# H26R00.net
KiCad netlist of a schematic drawn in EAGLE
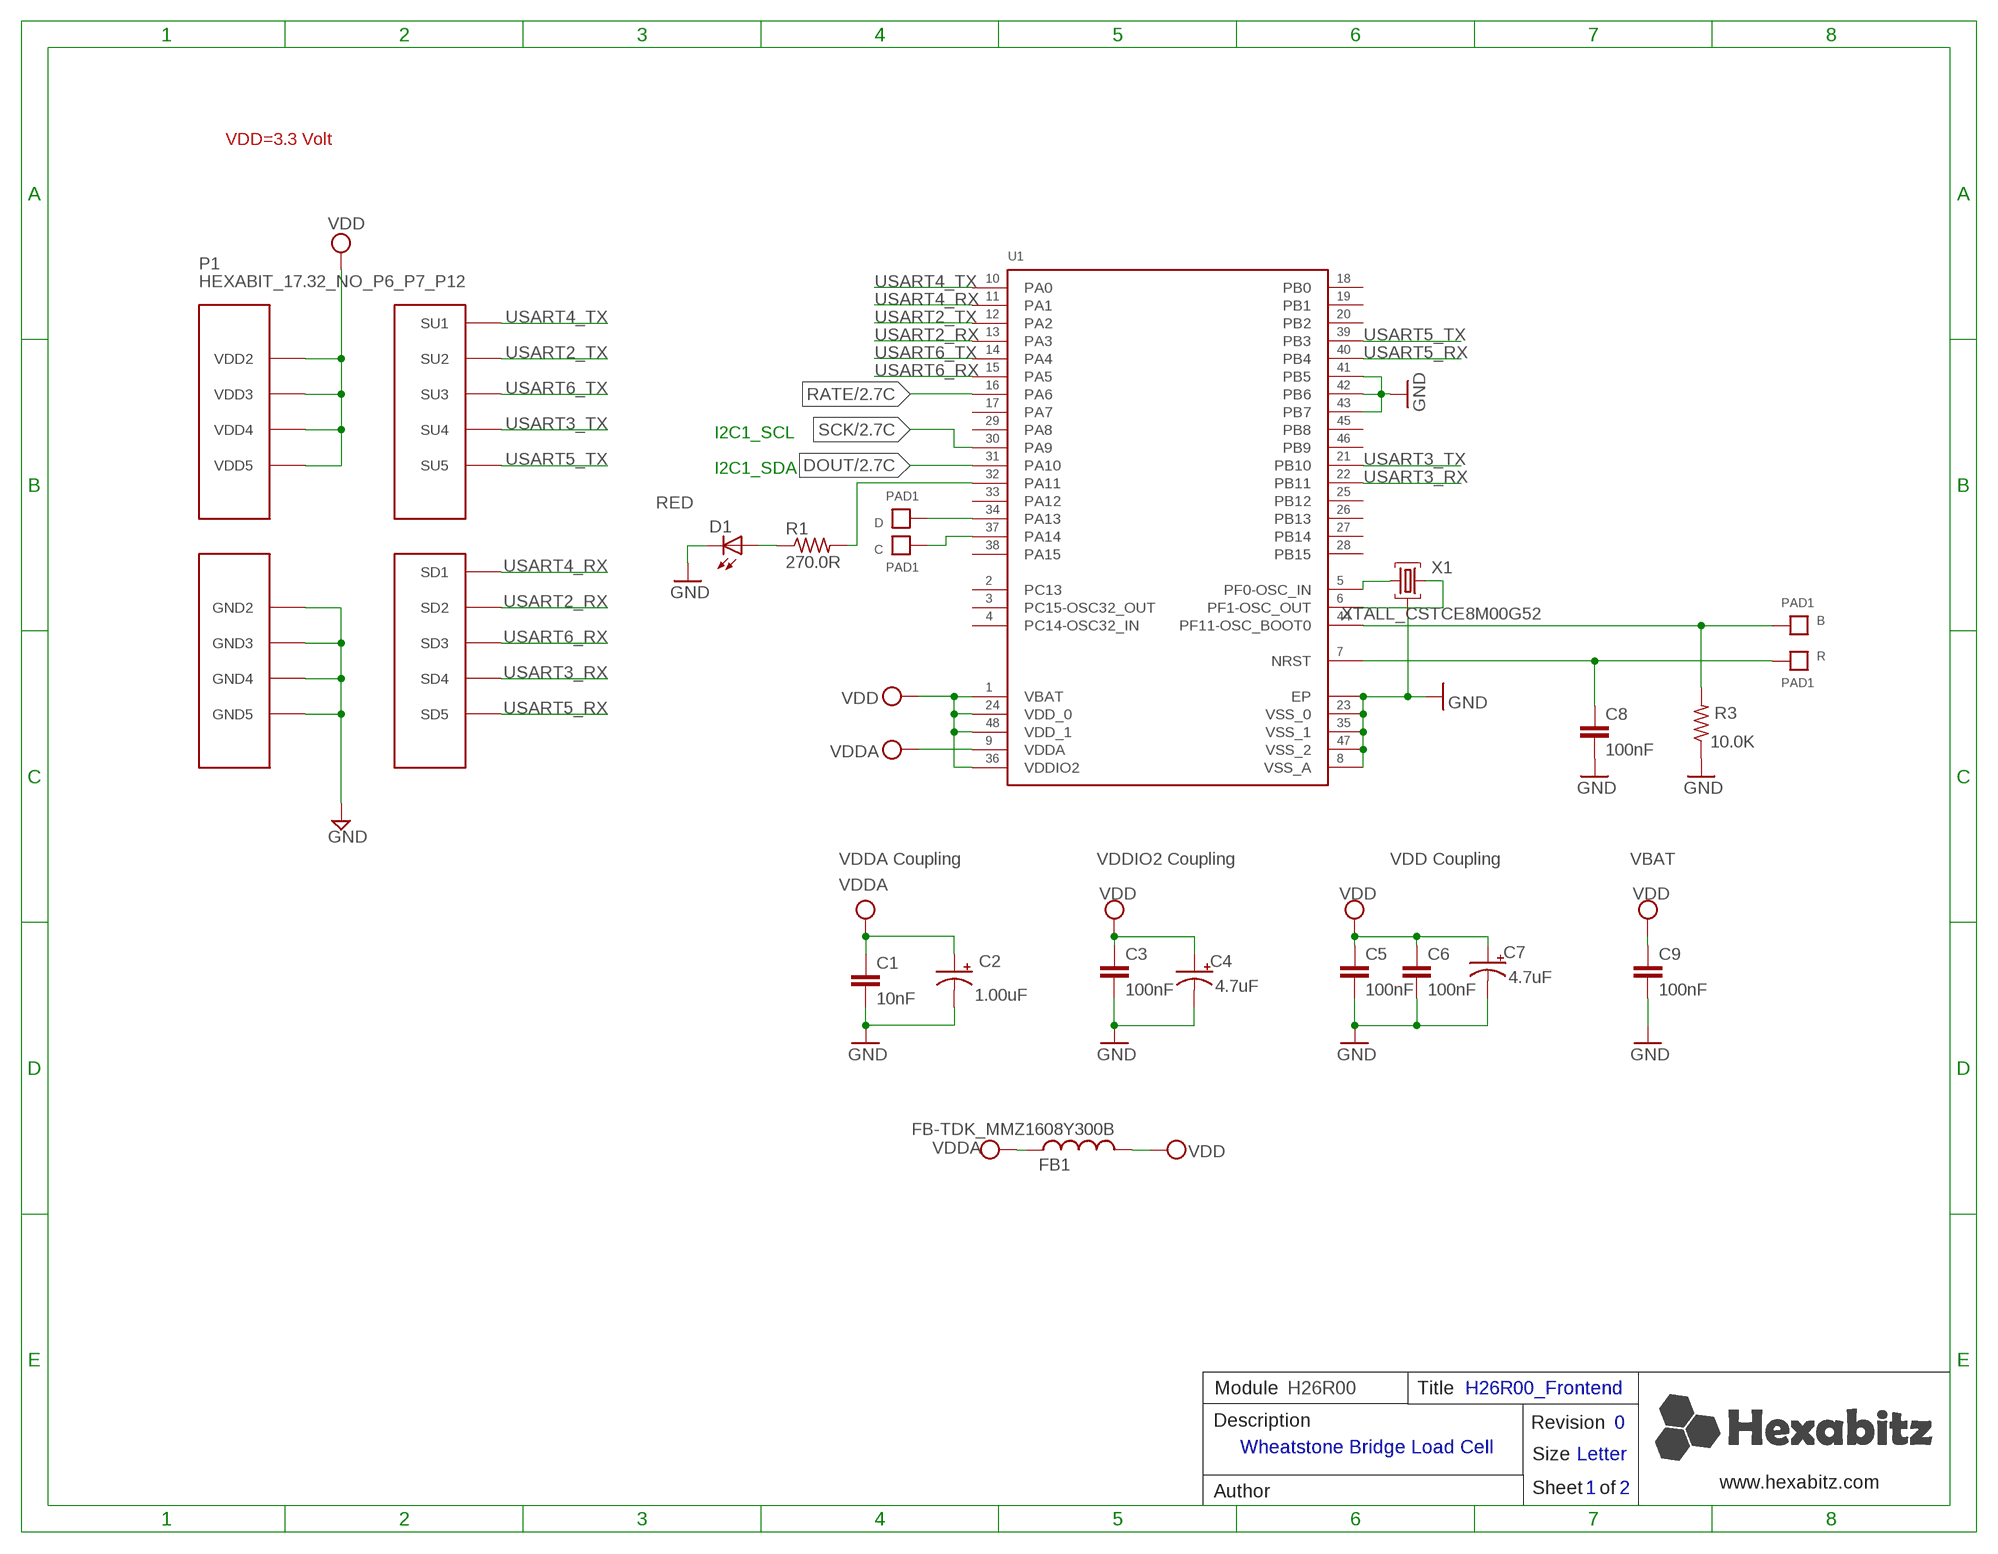
[diagram p0: schematic, sheet 1]
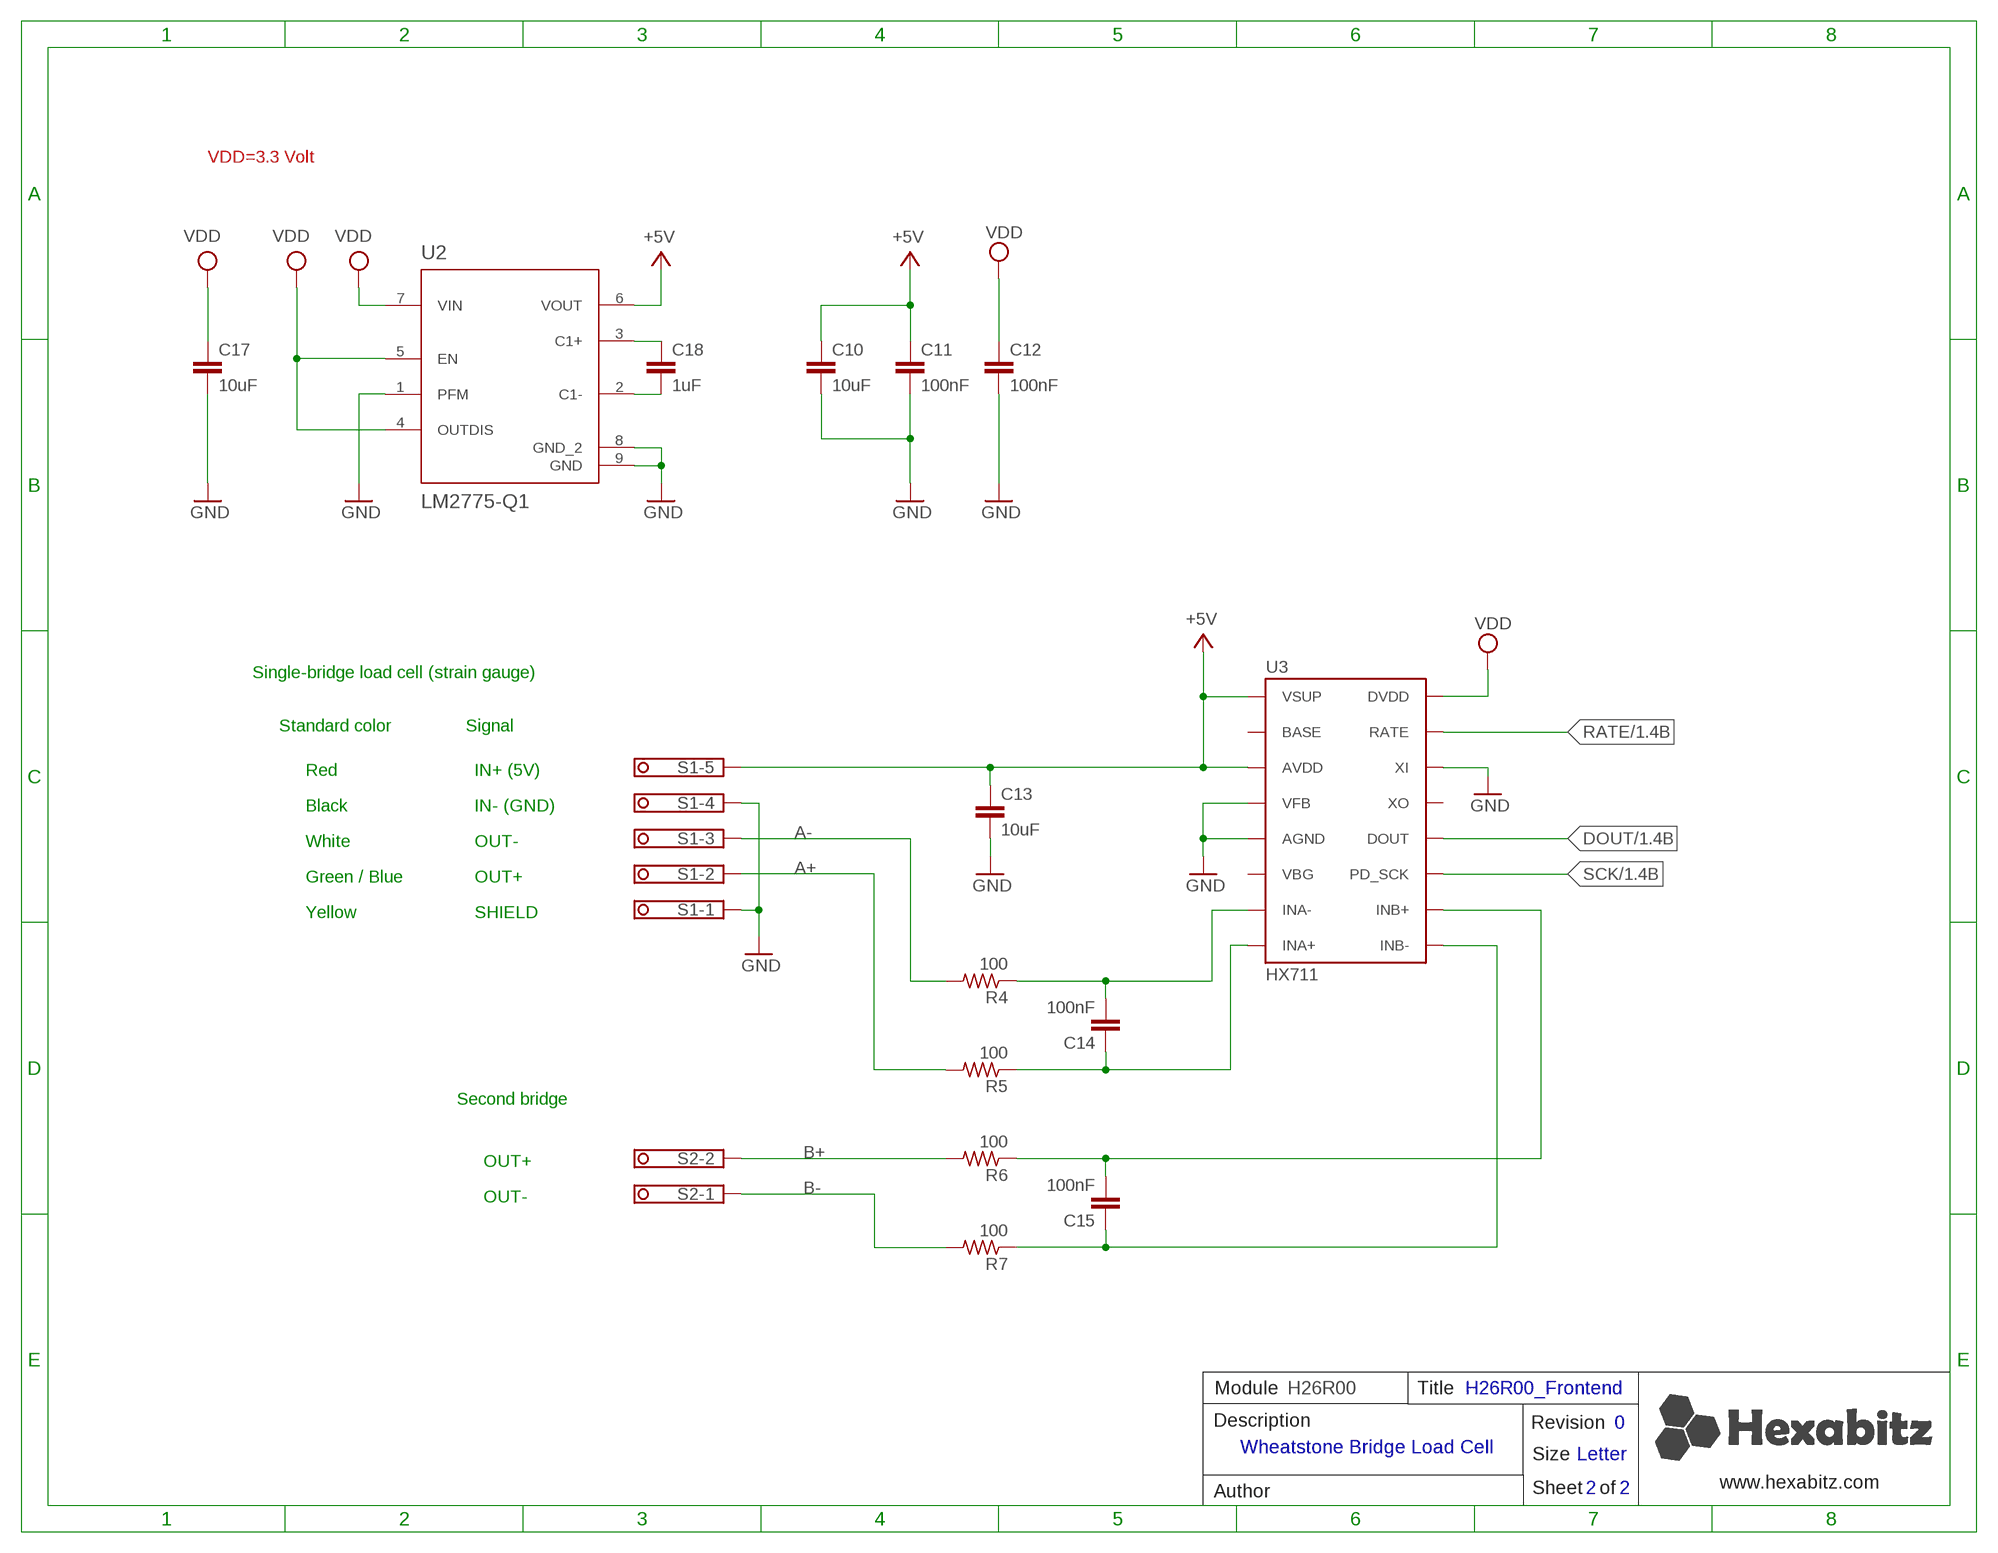
[diagram p1: schematic, sheet 2]

(export (version "E")
  (design (tool "Eeschema 10.0.6"))
  (components
    (comp (ref "C10")
      (value "10uF")
      (footprint "eagle-import:C-0603")
      (fields
        (field (name "CAPACITANCE") "10uF")
        (field (name "MFN") "Murarta")
        (field (name "MPN") "GRM188R61A106KE69D")
        (field (name "OCTOPART_URL") "https://octopart.com/grm188r61a106ke69d-murata-22851381?r=ap&s=o9t4ILLiSny6rfdd0oM5Kg")
        (field (name "TOLERANCE") "10%")
        (field (name "VOLTAGE_RATING") "10V")
      )
      (libsource (lib "eagle-import") (part "C-0603"))
    )
    (comp (ref "C11")
      (value "100nF")
      (footprint "eagle-import:C-0603")
      (fields
        (field (name "CAPACITANCE") "100nF")
        (field (name "MFN") "KEMET")
        (field (name "MPN") "C0603C104K8RACTU")
        (field (name "OCTOPART_URL") "https://octopart.com/c0603c104k8ractu-kemet-145075?r=sp&s=9bS9ASSwSEqMCE9KBEQZ0g")
        (field (name "TOLERANCE") "10%")
        (field (name "VOLTAGE_RATING") "10V")
      )
      (libsource (lib "eagle-import") (part "C-0603"))
    )
    (comp (ref "C12")
      (value "100nF")
      (footprint "eagle-import:C-0603")
      (fields
        (field (name "CAPACITANCE") "100nF")
        (field (name "MFN") "KEMET")
        (field (name "MPN") "C0603C104K8RACTU")
        (field (name "OCTOPART_URL") "https://octopart.com/c0603c104k8ractu-kemet-145075?r=sp&s=9bS9ASSwSEqMCE9KBEQZ0g")
        (field (name "TOLERANCE") "10%")
        (field (name "VOLTAGE_RATING") "10V")
      )
      (libsource (lib "eagle-import") (part "C-0603"))
    )
    (comp (ref "C13")
      (value "10uF")
      (footprint "eagle-import:C-0603")
      (fields
        (field (name "CAPACITANCE") "10uF")
        (field (name "MFN") "Murata")
        (field (name "MPN") "GRM188R61A106KE69D")
        (field (name "OCTOPART_URL") "https://octopart.com/grm188r61a106ke69d-murata-22851381?r=ap&s=o9t4ILLiSny6rfdd0oM5Kg")
        (field (name "TOLERANCE") "10%")
        (field (name "VOLTAGE_RATING") "10V")
      )
      (libsource (lib "eagle-import") (part "C-0603"))
    )
    (comp (ref "C14")
      (value "100nF")
      (footprint "eagle-import:C-0603")
      (fields
        (field (name "CAPACITANCE") "100nF")
        (field (name "MFN") "KEMET")
        (field (name "MPN") "C0603C104K8RACTU")
        (field (name "OCTOPART_URL") "https://octopart.com/c0603c104k8ractu-kemet-145075?r=sp&s=9bS9ASSwSEqMCE9KBEQZ0g")
        (field (name "TOLERANCE") "10V")
        (field (name "VOLTAGE_RATING") "10%")
      )
      (libsource (lib "eagle-import") (part "C-0603"))
    )
    (comp (ref "C15")
      (value "100nF")
      (footprint "eagle-import:C-0603")
      (fields
        (field (name "CAPACITANCE") "100nF")
        (field (name "MFN") "KEMET")
        (field (name "MPN") "C0603C104K8RACTU")
        (field (name "OCTOPART_URL") "https://octopart.com/c0603c104k8ractu-kemet-145075?r=sp&s=9bS9ASSwSEqMCE9KBEQZ0g")
        (field (name "TOLERANCE") "10V")
        (field (name "VOLTAGE_RATING") "10%")
      )
      (libsource (lib "eagle-import") (part "C-0603"))
    )
    (comp (ref "C17")
      (value "10uF")
      (footprint "eagle-import:C-0603")
      (fields
        (field (name "CAPACITANCE") "10uF")
        (field (name "MFN") "Murarta")
        (field (name "MPN") "GRM188R61A106KE69D")
        (field (name "OCTOPART_URL") "https://octopart.com/grm188r61a106ke69d-murata-22851381?r=ap&s=o9t4ILLiSny6rfdd0oM5Kg")
        (field (name "TOLERANCE") "10%")
        (field (name "VOLTAGE_RATING") "10V")
      )
      (libsource (lib "eagle-import") (part "C-0603"))
    )
    (comp (ref "C18")
      (value "1uF")
      (footprint "eagle-import:C-0603")
      (fields
        (field (name "CAPACITANCE") "1uF")
        (field (name "MFN") "Murarta")
        (field (name "MPN") "GRM188R61A105KA61J")
        (field (name "OCTOPART_URL") "https://octopart.com/grm188r61a105ka61j-murata-9221870?r=sp&s=wvtiDxTpS1CkWsFaa2pliQ")
        (field (name "TOLERANCE") "10%")
        (field (name "VOLTAGE_RATING") "10V")
      )
      (libsource (lib "eagle-import") (part "C-0603"))
    )
    (comp (ref "R4")
      (value "100")
      (footprint "eagle-import:R-0603")
      (fields
        (field (name "MFN") "Yageo")
        (field (name "MPN") "RC0603JR-07100RL")
        (field (name "OCTOPART_URL") "https://octopart.com/rc0603jr-07100rl-yageo-55458504?r=sp&s=j3XfnGiETZqzM9npqpV08Q")
        (field (name "RESISTANCE") "100")
        (field (name "TOLERANCE") "5%")
      )
      (libsource (lib "eagle-import") (part "R-0603"))
    )
    (comp (ref "R5")
      (value "100")
      (footprint "eagle-import:R-0603")
      (fields
        (field (name "MFN") "Yageo")
        (field (name "MPN") "RC0603JR-07100RL")
        (field (name "OCTOPART_URL") "https://octopart.com/rc0603jr-07100rl-yageo-55458504?r=sp&s=j3XfnGiETZqzM9npqpV08Q")
        (field (name "RESISTANCE") "100")
        (field (name "TOLERANCE") "5%")
      )
      (libsource (lib "eagle-import") (part "R-0603"))
    )
    (comp (ref "R6")
      (value "100")
      (footprint "eagle-import:R-0603")
      (fields
        (field (name "MFN") "Yageo")
        (field (name "MPN") "RC0603JR-07100RL")
        (field (name "OCTOPART_URL") "https://octopart.com/rc0603jr-07100rl-yageo-55458504?r=sp&s=j3XfnGiETZqzM9npqpV08Q")
        (field (name "RESISTANCE") "100")
        (field (name "TOLERANCE") "5%")
      )
      (libsource (lib "eagle-import") (part "R-0603"))
    )
    (comp (ref "R7")
      (value "100")
      (footprint "eagle-import:R-0603")
      (fields
        (field (name "MFN") "Yageo")
        (field (name "MPN") "RC0603JR-07100RL")
        (field (name "OCTOPART_URL") "https://octopart.com/rc0603jr-07100rl-yageo-55458504?r=sp&s=j3XfnGiETZqzM9npqpV08Q")
        (field (name "RESISTANCE") "100")
        (field (name "TOLERANCE") "5%")
      )
      (libsource (lib "eagle-import") (part "R-0603"))
    )
    (comp (ref "S1")
      (value "CON-PHOENIX-350_1751277")
      (footprint "eagle-import:CON-PHOENIX-350_1751277")
      (fields
        (field (name "MPN") "1984646")
        (field (name "MFN") "Phoenix Contact")
        (field (name "OCTOPART_URL") "https://octopart.com/1984646-phoenix+contact-50274?r=sp&s=drI_GVM4QHaL48lSCATrxQ")
      )
      (libsource (lib "eagle-import") (part "CON-PHOENIX-350_1751277"))
    )
    (comp (ref "S2")
      (value "CON-PHOENIX-350_1751248")
      (footprint "eagle-import:CON-PHOENIX-350_1751248")
      (fields
        (field (name "MPN") "1751251")
        (field (name "MFN") "Phoenix Contact")
        (field (name "MPN_1") "1984617")
        (field (name "OCTOPART_URL") "https://octopart.com/1984617-phoenix+contact-58834?r=sp&s=Ef_UaV1JSFmY0wggQyN1Mw")
      )
      (libsource (lib "eagle-import") (part "CON-PHOENIX-350_1751248"))
    )
    (comp (ref "U2")
      (value "LM2775-Q1")
      (footprint "eagle-import:DSG0008A")
      (fields (field (name "MANUFACTURER") "Texas Instruments") (field (name "MPN") "LM2775QDSGRQ1"))
      (libsource (lib "eagle-import") (part "LM2775QDSGRQ1"))
    )
    (comp (ref "U3")
      (value "HX711")
      (footprint "eagle-import:HX711_SO16")
      (libsource (lib "eagle-import") (part "HX711"))
    )
    (comp (ref "B")
      (value "PAD1")
      (footprint "eagle-import:PAD1")
      (libsource (lib "eagle-import") (part "PAD1"))
    )
    (comp (ref "C")
      (value "PAD1")
      (footprint "eagle-import:PAD1")
      (libsource (lib "eagle-import") (part "PAD1"))
    )
    (comp (ref "C1")
      (value "10nF")
      (footprint "eagle-import:C-0603")
      (fields
        (field (name "CAPACITANCE") "10nF")
        (field (name "MFN") "KEMET")
        (field (name "MPN") "C0603C103K5RACTU")
        (field (name "OCTOPART_URL") "https://octopart.com/c0603c103k5ractu-kemet-133094?r=sp&s=R_iPBxLnSmGqhkU2rIMFpg")
        (field (name "TOLERANCE") "10%")
        (field (name "VOLTAGE_RATING") "50V")
      )
      (libsource (lib "eagle-import") (part "C-0603"))
    )
    (comp (ref "C2")
      (value "1.00uF")
      (footprint "eagle-import:C-0805-POL")
      (fields
        (field (name "CAPACITANCE") "1.00uF")
        (field (name "MFN") "Yageo")
        (field (name "MPN") "CC0805KKX7R7BB105")
        (field (name "OCTOPART_URL") "https://octopart.com/cc0805kkx7r7bb105-yageo-8376555?r=sp&s=YKl1wwtkROau_X5nniH2ig")
        (field (name "TOLERANCE") "10%")
        (field (name "VOLTAGE_RATING") "16V")
      )
      (libsource (lib "eagle-import") (part "C-0805-POL"))
    )
    (comp (ref "C3")
      (value "100nF")
      (footprint "eagle-import:C-0603")
      (fields
        (field (name "CAPACITANCE") "100nF")
        (field (name "MFN") "KEMET")
        (field (name "MPN") "C0603C104K8RACTU")
        (field (name "OCTOPART_URL") "https://octopart.com/c0603c104k8ractu-kemet-145075?r=sp&s=9bS9ASSwSEqMCE9KBEQZ0g")
        (field (name "TOLERANCE") "10%")
        (field (name "VOLTAGE_RATING") "10V")
      )
      (libsource (lib "eagle-import") (part "C-0603"))
    )
    (comp (ref "C4")
      (value "4.7uF")
      (footprint "eagle-import:C-0805-POL")
      (fields
        (field (name "CAPACITANCE") "4.7uF")
        (field (name "MFN") "Murata")
        (field (name "MPN") "GRM21BC81E475KA12L")
        (field (name "OCTOPART_URL") "https://octopart.com/grm21bc81e475ka12l-murata-10331911?r=sp&s=RY3qZSD8T6mG6TC9CHI5qQ")
        (field (name "TOLERANCE") "10%")
        (field (name "VOLTAGE_RATING") "25V")
      )
      (libsource (lib "eagle-import") (part "C-0805-POL"))
    )
    (comp (ref "C5")
      (value "100nF")
      (footprint "eagle-import:C-0603")
      (fields
        (field (name "CAPACITANCE") "100nF")
        (field (name "MFN") "KEMET")
        (field (name "MPN") "C0603C104K8RACTU")
        (field (name "OCTOPART_URL") "https://octopart.com/c0603c104k8ractu-kemet-145075?r=sp&s=9bS9ASSwSEqMCE9KBEQZ0g")
        (field (name "TOLERANCE") "10%")
        (field (name "VOLTAGE_RATING") "10")
      )
      (libsource (lib "eagle-import") (part "C-0603"))
    )
    (comp (ref "C6")
      (value "100nF")
      (footprint "eagle-import:C-0603")
      (fields
        (field (name "CAPACITANCE") "100nF")
        (field (name "MFN") "KEMET")
        (field (name "MPN") "C0603C104K8RACTU")
        (field (name "OCTOPART_URL") "https://octopart.com/c0603c104k8ractu-kemet-145075?r=sp&s=9bS9ASSwSEqMCE9KBEQZ0g")
        (field (name "TOLERANCE") "10%")
        (field (name "VOLTAGE_RATING") "10V")
      )
      (libsource (lib "eagle-import") (part "C-0603"))
    )
    (comp (ref "C7")
      (value "4.7uF")
      (footprint "eagle-import:C-0805-POL")
      (fields
        (field (name "CAPACITANCE") "4.7uF")
        (field (name "MFN") "Murata")
        (field (name "MPN") "GRM21BC81E475KA12L")
        (field (name "OCTOPART_URL") "https://octopart.com/grm21bc81e475ka12l-murata-10331911?r=sp&s=RY3qZSD8T6mG6TC9CHI5qQ")
        (field (name "TOLERANCE") "10%")
        (field (name "VOLTAGE_RATING") "25V")
      )
      (libsource (lib "eagle-import") (part "C-0805-POL"))
    )
    (comp (ref "C8")
      (value "100nF")
      (footprint "eagle-import:C-0603")
      (fields
        (field (name "CAPACITANCE") "100nF")
        (field (name "MFN") "KEMET")
        (field (name "MPN") "C0603C104K8RACTU")
        (field (name "OCTOPART_URL") "https://octopart.com/c0603c104k8ractu-kemet-145075?r=sp&s=9bS9ASSwSEqMCE9KBEQZ0g")
        (field (name "TOLERANCE") "10%")
        (field (name "VOLTAGE_RATING") "10V")
      )
      (libsource (lib "eagle-import") (part "C-0603"))
    )
    (comp (ref "C9")
      (value "100nF")
      (footprint "eagle-import:C-0603")
      (fields
        (field (name "CAPACITANCE") "100nF")
        (field (name "MFN") "KEMET")
        (field (name "MPN") "C0603C104K8RACTU")
        (field (name "OCTOPART_URL") "https://octopart.com/c0603c104k8ractu-kemet-145075?r=sp&s=9bS9ASSwSEqMCE9KBEQZ0g")
        (field (name "TOLERANCE") "10V")
        (field (name "VOLTAGE_RATING") "10%")
      )
      (libsource (lib "eagle-import") (part "C-0603"))
    )
    (comp (ref "D")
      (value "PAD1")
      (footprint "eagle-import:PAD1")
      (libsource (lib "eagle-import") (part "PAD1"))
    )
    (comp (ref "D1")
      (value "RED")
      (footprint "eagle-import:VLMS1300-GS08")
      (fields
        (field (name "MPN") "VLMS1300-GS08")
        (field (name "MFN") "Vishay")
        (field (name "MPN_1") "VLMS1300-GS08")
        (field (name "OCTOPART_URL") "https://octopart.com/vlms1300-gs08-vishay-21709201?r=sp&s=_gcP4_q8T1SC6PJQPTQ9yA")
      )
      (libsource (lib "eagle-import") (part "VLMS1300-GS08"))
    )
    (comp (ref "FB1")
      (value "FB-TDK_MMZ1608Y300B")
      (footprint "eagle-import:FB-TDK_MMZ1608Y300B")
      (fields
        (field (name "MFN") "TDK ")
        (field (name "MPN") "MMZ1608Y300B")
        (field (name "OCTOPART_URL") "https://octopart.com/mmz1608y300b-tdk-368280?r=sp&s=cd9_2ZEqQ9q9UNBuQgHAiA")
      )
      (libsource (lib "eagle-import") (part "FB-TDK_MMZ1608Y300B"))
    )
    (comp (ref "P1")
      (value "HEXABIT_17.32_NO_P6_P7_P12")
      (footprint "eagle-import:HEXABIT_17.32_NO_P6_P7_P12")
      (libsource (lib "eagle-import") (part "HEXABIT_?_NO_P6_P7_P1217.32"))
    )
    (comp (ref "R")
      (value "PAD1")
      (footprint "eagle-import:PAD1")
      (libsource (lib "eagle-import") (part "PAD1"))
    )
    (comp (ref "R1")
      (value "270.0R")
      (footprint "eagle-import:R-0603")
      (fields
        (field (name "MFN") "Yageo")
        (field (name "MPN") "RC0603FR-07270RL")
        (field (name "OCTOPART_URL") "https://octopart.com/search?q=RC0603FR-07270RL&start=0")
        (field (name "RESISTANCE") "270.0 Ohm")
        (field (name "TOLERANCE") "1%")
      )
      (libsource (lib "eagle-import") (part "R-0603"))
    )
    (comp (ref "R3")
      (value "10.0K")
      (footprint "eagle-import:R-0603")
      (fields
        (field (name "MFN") "Yageo")
        (field (name "MPN") "RC0603JR-0710KL")
        (field (name "OCTOPART_URL") "https://octopart.com/search?q=RC0603JR-0710KL&start=0")
        (field (name "RESISTANCE") "10.0K Ohm")
        (field (name "TOLERANCE") "5%")
      )
      (libsource (lib "eagle-import") (part "R-0603"))
    )
    (comp (ref "U1")
      (value "STM32F091CBU6")
      (footprint "eagle-import:STM32F091CBU6")
      (libsource (lib "eagle-import") (part "STM32F091CBU6"))
    )
    (comp (ref "X1")
      (value "XTALL_CSTCE8M00G52")
      (footprint "eagle-import:XTALL_CSTCE8M00G52")
      (fields (field (name "MPN") "CSTCE8M00G52Z-R0"))
      (libsource (lib "eagle-import") (part "XTALL_CSTCE8M00G52"))
    )
  )
  (nets
    (net (code "1") (name "+5V") (class "Default")
      (node (ref "C10") (pin "1") (pinfunction "1_1") (pintype "passive"))
      (node (ref "C11") (pin "1") (pinfunction "1_1") (pintype "passive"))
      (node (ref "C13") (pin "1") (pinfunction "1_1") (pintype "passive"))
      (node (ref "S1") (pin "5") (pinfunction "K_5") (pintype "passive"))
      (node (ref "U2") (pin "6") (pinfunction "VOUT_6") (pintype "power_in"))
      (node (ref "U3") (pin "1") (pinfunction "VSUP_1") (pintype "bidirectional"))
      (node (ref "U3") (pin "3") (pinfunction "AVDD_3") (pintype "bidirectional"))
    )
    (net (code "2") (name "A+") (class "Default")
      (node (ref "R5") (pin "2") (pinfunction "2_2") (pintype "passive"))
      (node (ref "S1") (pin "2") (pinfunction "K_2") (pintype "passive"))
    )
    (net (code "3") (name "A-") (class "Default")
      (node (ref "R4") (pin "2") (pinfunction "2_2") (pintype "passive"))
      (node (ref "S1") (pin "3") (pinfunction "K_3") (pintype "passive"))
    )
    (net (code "4") (name "B+") (class "Default")
      (node (ref "R6") (pin "2") (pinfunction "2_2") (pintype "passive"))
      (node (ref "S2") (pin "2") (pinfunction "K_2") (pintype "passive"))
    )
    (net (code "5") (name "B-") (class "Default")
      (node (ref "R7") (pin "2") (pinfunction "2_2") (pintype "passive"))
      (node (ref "S2") (pin "1") (pinfunction "K_1") (pintype "passive"))
    )
    (net (code "6") (name "DOUT") (class "Default")
      (node (ref "U1") (pin "P$31") (pinfunction "PA10_P$31") (pintype "bidirectional"))
      (node (ref "U3") (pin "12") (pinfunction "DOUT_12") (pintype "bidirectional"))
    )
    (net (code "7") (name "GND") (class "Default")
      (node (ref "C1") (pin "2") (pinfunction "2_2") (pintype "passive"))
      (node (ref "C10") (pin "2") (pinfunction "2_2") (pintype "passive"))
      (node (ref "C11") (pin "2") (pinfunction "2_2") (pintype "passive"))
      (node (ref "C12") (pin "2") (pinfunction "2_2") (pintype "passive"))
      (node (ref "C13") (pin "2") (pinfunction "2_2") (pintype "passive"))
      (node (ref "C17") (pin "2") (pinfunction "2_2") (pintype "passive"))
      (node (ref "C2") (pin "2") (pinfunction "-_2") (pintype "passive"))
      (node (ref "C3") (pin "2") (pinfunction "2_2") (pintype "passive"))
      (node (ref "C4") (pin "2") (pinfunction "-_2") (pintype "passive"))
      (node (ref "C5") (pin "2") (pinfunction "2_2") (pintype "passive"))
      (node (ref "C6") (pin "2") (pinfunction "2_2") (pintype "passive"))
      (node (ref "C7") (pin "2") (pinfunction "-_2") (pintype "passive"))
      (node (ref "C8") (pin "2") (pinfunction "2_2") (pintype "passive"))
      (node (ref "C9") (pin "2") (pinfunction "2_2") (pintype "passive"))
      (node (ref "D1") (pin "C") (pinfunction "C_C") (pintype "passive"))
      (node (ref "P1") (pin "PAD_PD10") (pinfunction "GND4_PAD_PD10") (pintype "power_in"))
      (node (ref "P1") (pin "PAD_PD11") (pinfunction "GND5_PAD_PD11") (pintype "power_in"))
      (node (ref "P1") (pin "PAD_PD8") (pinfunction "GND2_PAD_PD8") (pintype "power_in"))
      (node (ref "P1") (pin "PAD_PD9") (pinfunction "GND3_PAD_PD9") (pintype "power_in"))
      (node (ref "R3") (pin "1") (pinfunction "1_1") (pintype "passive"))
      (node (ref "S1") (pin "1") (pinfunction "K_1") (pintype "passive"))
      (node (ref "S1") (pin "4") (pinfunction "K_4") (pintype "passive"))
      (node (ref "U1") (pin "EP") (pinfunction "EP_EP") (pintype "power_in"))
      (node (ref "U1") (pin "P$23") (pinfunction "VSS_0_P$23") (pintype "power_in"))
      (node (ref "U1") (pin "P$35") (pinfunction "VSS_1_P$35") (pintype "power_in"))
      (node (ref "U1") (pin "P$41") (pinfunction "PB5_P$41") (pintype "bidirectional"))
      (node (ref "U1") (pin "P$42") (pinfunction "PB6_P$42") (pintype "bidirectional"))
      (node (ref "U1") (pin "P$43") (pinfunction "PB7_P$43") (pintype "bidirectional"))
      (node (ref "U1") (pin "P$47") (pinfunction "VSS_2_P$47") (pintype "power_in"))
      (node (ref "U1") (pin "P$8") (pinfunction "VSS_A_P$8") (pintype "power_in"))
      (node (ref "U2") (pin "1") (pinfunction "PFM_1") (pintype "input"))
      (node (ref "U2") (pin "8") (pinfunction "GND_2_8") (pintype "power_in"))
      (node (ref "U2") (pin "9") (pinfunction "GND_9") (pintype "power_in"))
      (node (ref "U3") (pin "14") (pinfunction "XI_14") (pintype "bidirectional"))
      (node (ref "U3") (pin "4") (pinfunction "VFB_4") (pintype "bidirectional"))
      (node (ref "U3") (pin "5") (pinfunction "AGND_5") (pintype "bidirectional"))
      (node (ref "X1") (pin "P$2") (pinfunction "2_P$2") (pintype "passive"))
    )
    (net (code "8") (name "Net-(D1-PadA)") (class "Default")
      (node (ref "D1") (pin "A") (pinfunction "A_A") (pintype "passive"))
      (node (ref "R1") (pin "1") (pinfunction "1_1") (pintype "passive"))
    )
    (net (code "9") (name "Net-(U1-NRST)") (class "Default")
      (node (ref "C8") (pin "1") (pinfunction "1_1") (pintype "passive"))
      (node (ref "R") (pin "P$1") (pinfunction "P$1_P$1") (pintype "passive"))
      (node (ref "R") (pin "P$2") (pinfunction "P$1_P$2") (pintype "passive"))
      (node (ref "U1") (pin "P$7") (pinfunction "NRST_P$7") (pintype "passive"))
    )
    (net (code "10") (name "Net-(U1-PA11)") (class "Default")
      (node (ref "R1") (pin "2") (pinfunction "2_2") (pintype "passive"))
      (node (ref "U1") (pin "P$32") (pinfunction "PA11_P$32") (pintype "bidirectional"))
    )
    (net (code "11") (name "Net-(U1-PA13)") (class "Default")
      (node (ref "D") (pin "P$1") (pinfunction "P$1_P$1") (pintype "passive"))
      (node (ref "D") (pin "P$2") (pinfunction "P$1_P$2") (pintype "passive"))
      (node (ref "U1") (pin "P$34") (pinfunction "PA13_P$34") (pintype "bidirectional"))
    )
    (net (code "12") (name "Net-(U1-PA14)") (class "Default")
      (node (ref "C") (pin "P$1") (pinfunction "P$1_P$1") (pintype "passive"))
      (node (ref "C") (pin "P$2") (pinfunction "P$1_P$2") (pintype "passive"))
      (node (ref "U1") (pin "P$37") (pinfunction "PA14_P$37") (pintype "bidirectional"))
    )
    (net (code "13") (name "Net-(U1-PF0-OSC_IN)") (class "Default")
      (node (ref "U1") (pin "P$5") (pinfunction "PF0-OSC_IN_P$5") (pintype "bidirectional"))
      (node (ref "X1") (pin "P$1") (pinfunction "1_P$1") (pintype "passive"))
    )
    (net (code "14") (name "Net-(U1-PF1-OSC_OUT)") (class "Default")
      (node (ref "U1") (pin "P$6") (pinfunction "PF1-OSC_OUT_P$6") (pintype "bidirectional"))
      (node (ref "X1") (pin "P$3") (pinfunction "3_P$3") (pintype "passive"))
    )
    (net (code "15") (name "Net-(U1-PF11-OSC_BOOT0)") (class "Default")
      (node (ref "B") (pin "P$1") (pinfunction "P$1_P$1") (pintype "passive"))
      (node (ref "B") (pin "P$2") (pinfunction "P$1_P$2") (pintype "passive"))
      (node (ref "R3") (pin "2") (pinfunction "2_2") (pintype "passive"))
      (node (ref "U1") (pin "P$44") (pinfunction "PF11-OSC_BOOT0_P$44") (pintype "bidirectional"))
    )
    (net (code "16") (name "Net-(U2-C1+)") (class "Default")
      (node (ref "C18") (pin "1") (pinfunction "1_1") (pintype "passive"))
      (node (ref "U2") (pin "3") (pinfunction "C1+_3") (pintype "power_in"))
    )
    (net (code "17") (name "Net-(U2-C1-)") (class "Default")
      (node (ref "C18") (pin "2") (pinfunction "2_2") (pintype "passive"))
      (node (ref "U2") (pin "2") (pinfunction "C1-_2") (pintype "power_in"))
    )
    (net (code "18") (name "Net-(U3-INA+)") (class "Default")
      (node (ref "C14") (pin "1") (pinfunction "1_1") (pintype "passive"))
      (node (ref "R5") (pin "1") (pinfunction "1_1") (pintype "passive"))
      (node (ref "U3") (pin "8") (pinfunction "INA+_8") (pintype "bidirectional"))
    )
    (net (code "19") (name "Net-(U3-INA-)") (class "Default")
      (node (ref "C14") (pin "2") (pinfunction "2_2") (pintype "passive"))
      (node (ref "R4") (pin "1") (pinfunction "1_1") (pintype "passive"))
      (node (ref "U3") (pin "7") (pinfunction "INA-_7") (pintype "bidirectional"))
    )
    (net (code "20") (name "Net-(U3-INB+)") (class "Default")
      (node (ref "C15") (pin "2") (pinfunction "2_2") (pintype "passive"))
      (node (ref "R6") (pin "1") (pinfunction "1_1") (pintype "passive"))
      (node (ref "U3") (pin "10") (pinfunction "INB+_10") (pintype "bidirectional"))
    )
    (net (code "21") (name "Net-(U3-INB-)") (class "Default")
      (node (ref "C15") (pin "1") (pinfunction "1_1") (pintype "passive"))
      (node (ref "R7") (pin "1") (pinfunction "1_1") (pintype "passive"))
      (node (ref "U3") (pin "9") (pinfunction "INB-_9") (pintype "bidirectional"))
    )
    (net (code "22") (name "RATE") (class "Default")
      (node (ref "U1") (pin "P$16") (pinfunction "PA6_P$16") (pintype "bidirectional"))
      (node (ref "U3") (pin "15") (pinfunction "RATE_15") (pintype "bidirectional"))
    )
    (net (code "23") (name "SCK") (class "Default")
      (node (ref "U1") (pin "P$30") (pinfunction "PA9_P$30") (pintype "bidirectional"))
      (node (ref "U3") (pin "11") (pinfunction "PD_SCK_11") (pintype "bidirectional"))
    )
    (net (code "24") (name "USART2_RX") (class "Default")
      (node (ref "P1") (pin "PAD_PD2") (pinfunction "SD2_PAD_PD2") (pintype "bidirectional"))
      (node (ref "U1") (pin "P$13") (pinfunction "PA3_P$13") (pintype "bidirectional"))
    )
    (net (code "25") (name "USART2_TX") (class "Default")
      (node (ref "P1") (pin "PAD_PU2") (pinfunction "SU2_PAD_PU2") (pintype "bidirectional"))
      (node (ref "U1") (pin "P$12") (pinfunction "PA2_P$12") (pintype "bidirectional"))
    )
    (net (code "26") (name "USART3_RX") (class "Default")
      (node (ref "P1") (pin "PAD_PD4") (pinfunction "SD4_PAD_PD4") (pintype "bidirectional"))
      (node (ref "U1") (pin "P$22") (pinfunction "PB11_P$22") (pintype "bidirectional"))
    )
    (net (code "27") (name "USART3_TX") (class "Default")
      (node (ref "P1") (pin "PAD_PU4") (pinfunction "SU4_PAD_PU4") (pintype "bidirectional"))
      (node (ref "U1") (pin "P$21") (pinfunction "PB10_P$21") (pintype "bidirectional"))
    )
    (net (code "28") (name "USART4_RX") (class "Default")
      (node (ref "P1") (pin "PAD_PD1") (pinfunction "SD1_PAD_PD1") (pintype "bidirectional"))
      (node (ref "U1") (pin "P$11") (pinfunction "PA1_P$11") (pintype "bidirectional"))
    )
    (net (code "29") (name "USART4_TX") (class "Default")
      (node (ref "P1") (pin "PAD_PU1") (pinfunction "SU1_PAD_PU1") (pintype "bidirectional"))
      (node (ref "U1") (pin "P$10") (pinfunction "PA0_P$10") (pintype "bidirectional"))
    )
    (net (code "30") (name "USART5_RX") (class "Default")
      (node (ref "P1") (pin "PAD_PD5") (pinfunction "SD5_PAD_PD5") (pintype "bidirectional"))
      (node (ref "U1") (pin "P$40") (pinfunction "PB4_P$40") (pintype "bidirectional"))
    )
    (net (code "31") (name "USART5_TX") (class "Default")
      (node (ref "P1") (pin "PAD_PU5") (pinfunction "SU5_PAD_PU5") (pintype "bidirectional"))
      (node (ref "U1") (pin "P$39") (pinfunction "PB3_P$39") (pintype "bidirectional"))
    )
    (net (code "32") (name "USART6_RX") (class "Default")
      (node (ref "P1") (pin "PAD_PD3") (pinfunction "SD3_PAD_PD3") (pintype "bidirectional"))
      (node (ref "U1") (pin "P$15") (pinfunction "PA5_P$15") (pintype "bidirectional"))
    )
    (net (code "33") (name "USART6_TX") (class "Default")
      (node (ref "P1") (pin "PAD_PU3") (pinfunction "SU3_PAD_PU3") (pintype "bidirectional"))
      (node (ref "U1") (pin "P$14") (pinfunction "PA4_P$14") (pintype "bidirectional"))
    )
    (net (code "34") (name "VDD") (class "Default")
      (node (ref "C12") (pin "1") (pinfunction "1_1") (pintype "passive"))
      (node (ref "C17") (pin "1") (pinfunction "1_1") (pintype "passive"))
      (node (ref "C3") (pin "1") (pinfunction "1_1") (pintype "passive"))
      (node (ref "C4") (pin "1") (pinfunction "+_1") (pintype "passive"))
      (node (ref "C5") (pin "1") (pinfunction "1_1") (pintype "passive"))
      (node (ref "C6") (pin "1") (pinfunction "1_1") (pintype "passive"))
      (node (ref "C7") (pin "1") (pinfunction "+_1") (pintype "passive"))
      (node (ref "C9") (pin "1") (pinfunction "1_1") (pintype "passive"))
      (node (ref "FB1") (pin "2") (pinfunction "2_2") (pintype "passive"))
      (node (ref "P1") (pin "PAD_PU10") (pinfunction "VDD4_PAD_PU10") (pintype "power_in"))
      (node (ref "P1") (pin "PAD_PU11") (pinfunction "VDD5_PAD_PU11") (pintype "power_in"))
      (node (ref "P1") (pin "PAD_PU8") (pinfunction "VDD2_PAD_PU8") (pintype "power_in"))
      (node (ref "P1") (pin "PAD_PU9") (pinfunction "VDD3_PAD_PU9") (pintype "power_in"))
      (node (ref "U1") (pin "P$1") (pinfunction "VBAT_P$1") (pintype "power_in"))
      (node (ref "U1") (pin "P$24") (pinfunction "VDD_0_P$24") (pintype "power_in"))
      (node (ref "U1") (pin "P$36") (pinfunction "VDDIO2_P$36") (pintype "power_in"))
      (node (ref "U1") (pin "P$48") (pinfunction "VDD_1_P$48") (pintype "power_in"))
      (node (ref "U2") (pin "4") (pinfunction "OUTDIS_4") (pintype "input"))
      (node (ref "U2") (pin "5") (pinfunction "EN_5") (pintype "input"))
      (node (ref "U2") (pin "7") (pinfunction "VIN_7") (pintype "power_in"))
      (node (ref "U3") (pin "16") (pinfunction "DVDD_16") (pintype "bidirectional"))
    )
    (net (code "35") (name "VDDA") (class "Default")
      (node (ref "C1") (pin "1") (pinfunction "1_1") (pintype "passive"))
      (node (ref "C2") (pin "1") (pinfunction "+_1") (pintype "passive"))
      (node (ref "FB1") (pin "1") (pinfunction "1_1") (pintype "passive"))
      (node (ref "U1") (pin "P$9") (pinfunction "VDDA_P$9") (pintype "power_in"))
    )
    (net (code "36") (name "unconnected-(U1-PA7-PadP$17)") (class "Default")
      (node (ref "U1") (pin "P$17") (pinfunction "PA7_P$17") (pintype "bidirectional"))
    )
    (net (code "37") (name "unconnected-(U1-PA8-PadP$29)") (class "Default")
      (node (ref "U1") (pin "P$29") (pinfunction "PA8_P$29") (pintype "bidirectional"))
    )
    (net (code "38") (name "unconnected-(U1-PA12-PadP$33)") (class "Default")
      (node (ref "U1") (pin "P$33") (pinfunction "PA12_P$33") (pintype "bidirectional"))
    )
    (net (code "39") (name "unconnected-(U1-PA15-PadP$38)") (class "Default")
      (node (ref "U1") (pin "P$38") (pinfunction "PA15_P$38") (pintype "bidirectional"))
    )
    (net (code "40") (name "unconnected-(U1-PB0-PadP$18)") (class "Default")
      (node (ref "U1") (pin "P$18") (pinfunction "PB0_P$18") (pintype "bidirectional"))
    )
    (net (code "41") (name "unconnected-(U1-PB1-PadP$19)") (class "Default")
      (node (ref "U1") (pin "P$19") (pinfunction "PB1_P$19") (pintype "bidirectional"))
    )
    (net (code "42") (name "unconnected-(U1-PB2-PadP$20)") (class "Default")
      (node (ref "U1") (pin "P$20") (pinfunction "PB2_P$20") (pintype "bidirectional"))
    )
    (net (code "43") (name "unconnected-(U1-PB8-PadP$45)") (class "Default")
      (node (ref "U1") (pin "P$45") (pinfunction "PB8_P$45") (pintype "bidirectional"))
    )
    (net (code "44") (name "unconnected-(U1-PB9-PadP$46)") (class "Default")
      (node (ref "U1") (pin "P$46") (pinfunction "PB9_P$46") (pintype "bidirectional"))
    )
    (net (code "45") (name "unconnected-(U1-PB12-PadP$25)") (class "Default")
      (node (ref "U1") (pin "P$25") (pinfunction "PB12_P$25") (pintype "bidirectional"))
    )
    (net (code "46") (name "unconnected-(U1-PB13-PadP$26)") (class "Default")
      (node (ref "U1") (pin "P$26") (pinfunction "PB13_P$26") (pintype "bidirectional"))
    )
    (net (code "47") (name "unconnected-(U1-PB14-PadP$27)") (class "Default")
      (node (ref "U1") (pin "P$27") (pinfunction "PB14_P$27") (pintype "bidirectional"))
    )
    (net (code "48") (name "unconnected-(U1-PB15-PadP$28)") (class "Default")
      (node (ref "U1") (pin "P$28") (pinfunction "PB15_P$28") (pintype "bidirectional"))
    )
    (net (code "49") (name "unconnected-(U1-PC13-PadP$2)") (class "Default")
      (node (ref "U1") (pin "P$2") (pinfunction "PC13_P$2") (pintype "bidirectional"))
    )
    (net (code "50") (name "unconnected-(U1-PC14-OSC32_IN-PadP$3)") (class "Default")
      (node (ref "U1") (pin "P$3") (pinfunction "PC14-OSC32_IN_P$3") (pintype "bidirectional"))
    )
    (net (code "51") (name "unconnected-(U1-PC15-OSC32_OUT-PadP$4)") (class "Default")
      (node (ref "U1") (pin "P$4") (pinfunction "PC15-OSC32_OUT_P$4") (pintype "bidirectional"))
    )
    (net (code "52") (name "unconnected-(U3-BASE-Pad2)") (class "Default")
      (node (ref "U3") (pin "2") (pinfunction "BASE_2") (pintype "bidirectional"))
    )
    (net (code "53") (name "unconnected-(U3-VBG-Pad6)") (class "Default")
      (node (ref "U3") (pin "6") (pinfunction "VBG_6") (pintype "bidirectional"))
    )
    (net (code "54") (name "unconnected-(U3-XO-Pad13)") (class "Default")
      (node (ref "U3") (pin "13") (pinfunction "XO_13") (pintype "bidirectional"))
    )
  )
)
